# fanController.net
KiCad netlist of a schematic drawn in EAGLE
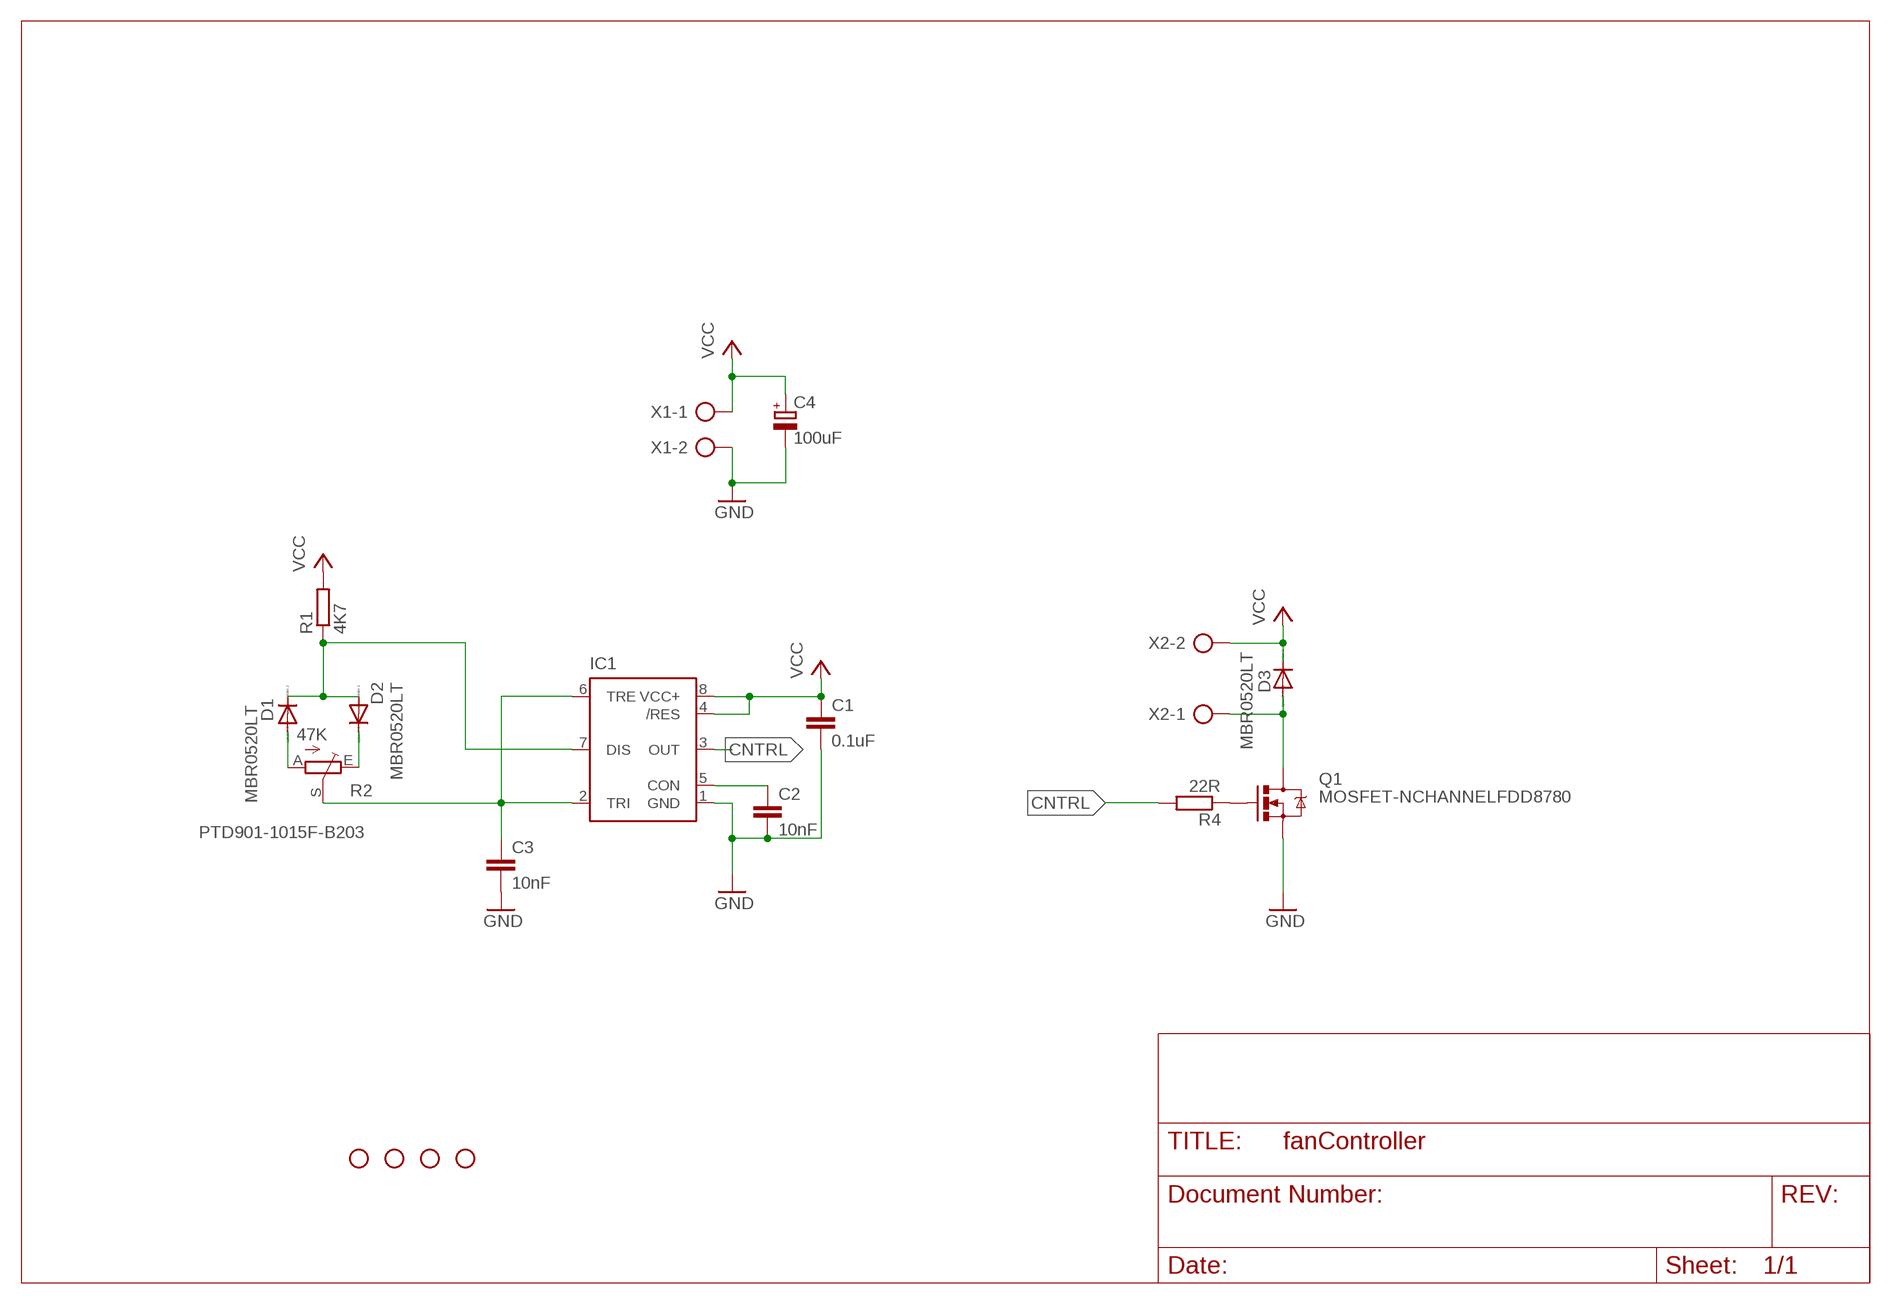
[diagram p0: schematic, sheet 1]

(export (version "E")
  (design (tool "Eeschema 10.0.6"))
  (components
    (comp (ref "C1")
      (value "0.1uF")
      (footprint "eagle-import:C0805")
      (libsource (lib "eagle-import") (part "C-EUC0805"))
    )
    (comp (ref "C2")
      (value "10nF")
      (footprint "eagle-import:C0805")
      (libsource (lib "eagle-import") (part "C-EUC0805"))
    )
    (comp (ref "C3")
      (value "10nF")
      (footprint "eagle-import:C0805")
      (libsource (lib "eagle-import") (part "C-EUC0805"))
    )
    (comp (ref "C4")
      (value "100uF")
      (footprint "eagle-import:PANASONIC_D")
      (libsource (lib "eagle-import") (part "CPOL-EUD"))
    )
    (comp (ref "D1")
      (value "MBR0520LT")
      (footprint "eagle-import:SOD123")
      (libsource (lib "eagle-import") (part "MBR0520LT"))
    )
    (comp (ref "D2")
      (value "MBR0520LT")
      (footprint "eagle-import:SOD123")
      (libsource (lib "eagle-import") (part "MBR0520LT"))
    )
    (comp (ref "D3")
      (value "MBR0520LT")
      (footprint "eagle-import:SOD123")
      (libsource (lib "eagle-import") (part "MBR0520LT"))
    )
    (comp (ref "IC1")
      (value "NE555D")
      (footprint "eagle-import:SO08")
      (libsource (lib "eagle-import") (part "NE555D"))
    )
    (comp (ref "Q1")
      (value "MOSFET-NCHANNELFDD8780")
      (footprint "eagle-import:DPAK")
      (libsource (lib "eagle-import") (part "MOSFET-NCHANNELFDD8780"))
    )
    (comp (ref "R1")
      (value "4K7")
      (footprint "eagle-import:M0805")
      (libsource (lib "eagle-import") (part "R-EU_M0805"))
    )
    (comp (ref "R2")
      (value "47K")
      (footprint "eagle-import:B64Y")
      (libsource (lib "eagle-import") (part "TRIM_EU-B64Y"))
    )
    (comp (ref "R4")
      (value "22R")
      (footprint "eagle-import:M0805")
      (libsource (lib "eagle-import") (part "R-EU_M0805"))
    )
    (comp (ref "STANDOFF1")
      (value "STAND-OFFTIGHT")
      (footprint "eagle-import:STAND-OFF-TIGHT")
      (libsource (lib "eagle-import") (part "STAND-OFFTIGHT"))
    )
    (comp (ref "STANDOFF2")
      (value "STAND-OFFTIGHT")
      (footprint "eagle-import:STAND-OFF-TIGHT")
      (libsource (lib "eagle-import") (part "STAND-OFFTIGHT"))
    )
    (comp (ref "STANDOFF3")
      (value "STAND-OFFTIGHT")
      (footprint "eagle-import:STAND-OFF-TIGHT")
      (libsource (lib "eagle-import") (part "STAND-OFFTIGHT"))
    )
    (comp (ref "STANDOFF4")
      (value "STAND-OFFTIGHT")
      (footprint "eagle-import:STAND-OFF-TIGHT")
      (libsource (lib "eagle-import") (part "STAND-OFFTIGHT"))
    )
    (comp (ref "X1")
      (value "AK500/2")
      (footprint "eagle-import:AK500_2")
      (libsource (lib "eagle-import") (part "AK500/2"))
    )
    (comp (ref "X2")
      (value "AK500/2")
      (footprint "eagle-import:AK500_2")
      (libsource (lib "eagle-import") (part "AK500/2"))
    )
  )
  (nets
    (net (code "1") (name "CNTRL") (class "Default")
      (node (ref "IC1") (pin "3") (pinfunction "OUT_3") (pintype "output"))
      (node (ref "R4") (pin "2") (pinfunction "2_2") (pintype "passive"))
    )
    (net (code "2") (name "GND") (class "Default")
      (node (ref "C1") (pin "2") (pinfunction "2_2") (pintype "passive"))
      (node (ref "C2") (pin "2") (pinfunction "2_2") (pintype "passive"))
      (node (ref "C3") (pin "2") (pinfunction "2_2") (pintype "passive"))
      (node (ref "C4") (pin "-") (pinfunction "-_-") (pintype "passive"))
      (node (ref "IC1") (pin "1") (pinfunction "GND_1") (pintype "power_in"))
      (node (ref "Q1") (pin "3") (pinfunction "S_3") (pintype "passive"))
      (node (ref "X1") (pin "2") (pinfunction "KL_2") (pintype "passive"))
    )
    (net (code "3") (name "Net-(D1-PadA)") (class "Default")
      (node (ref "D1") (pin "A") (pinfunction "A_A") (pintype "passive"))
      (node (ref "R2") (pin "A") (pinfunction "A_A") (pintype "passive"))
    )
    (net (code "4") (name "Net-(D2-PadC)") (class "Default")
      (node (ref "D2") (pin "C") (pinfunction "C_C") (pintype "passive"))
      (node (ref "R2") (pin "E") (pinfunction "E_E") (pintype "passive"))
    )
    (net (code "5") (name "Net-(IC1-CON)") (class "Default")
      (node (ref "C2") (pin "1") (pinfunction "1_1") (pintype "passive"))
      (node (ref "IC1") (pin "5") (pinfunction "CON_5") (pintype "input"))
    )
    (net (code "6") (name "Net-(IC1-DIS)") (class "Default")
      (node (ref "D1") (pin "C") (pinfunction "C_C") (pintype "passive"))
      (node (ref "D2") (pin "A") (pinfunction "A_A") (pintype "passive"))
      (node (ref "IC1") (pin "7") (pinfunction "DIS_7") (pintype "input"))
      (node (ref "R1") (pin "1") (pinfunction "1_1") (pintype "passive"))
    )
    (net (code "7") (name "Net-(IC1-TRE)") (class "Default")
      (node (ref "C3") (pin "1") (pinfunction "1_1") (pintype "passive"))
      (node (ref "IC1") (pin "2") (pinfunction "TRI_2") (pintype "input"))
      (node (ref "IC1") (pin "6") (pinfunction "TRE_6") (pintype "input"))
      (node (ref "R2") (pin "S") (pinfunction "S_S") (pintype "passive"))
    )
    (net (code "8") (name "Net-(Q1-D)") (class "Default")
      (node (ref "D3") (pin "A") (pinfunction "A_A") (pintype "passive"))
      (node (ref "Q1") (pin "4") (pinfunction "D_4") (pintype "passive"))
      (node (ref "X2") (pin "1") (pinfunction "KL_1") (pintype "passive"))
    )
    (net (code "9") (name "Net-(Q1-G)") (class "Default")
      (node (ref "Q1") (pin "1") (pinfunction "G_1") (pintype "passive"))
      (node (ref "R4") (pin "1") (pinfunction "1_1") (pintype "passive"))
    )
    (net (code "10") (name "VCC") (class "Default")
      (node (ref "C1") (pin "1") (pinfunction "1_1") (pintype "passive"))
      (node (ref "C4") (pin "+") (pinfunction "+_+") (pintype "passive"))
      (node (ref "D3") (pin "C") (pinfunction "C_C") (pintype "passive"))
      (node (ref "IC1") (pin "4") (pinfunction "/RES_4") (pintype "input"))
      (node (ref "IC1") (pin "8") (pinfunction "VCC+_8") (pintype "power_in"))
      (node (ref "R1") (pin "2") (pinfunction "2_2") (pintype "passive"))
      (node (ref "X1") (pin "1") (pinfunction "KL_1") (pintype "passive"))
      (node (ref "X2") (pin "2") (pinfunction "KL_2") (pintype "passive"))
    )
  )
)
